# Sheet_3.net
KiCad netlist of a schematic drawn in Altium Designer
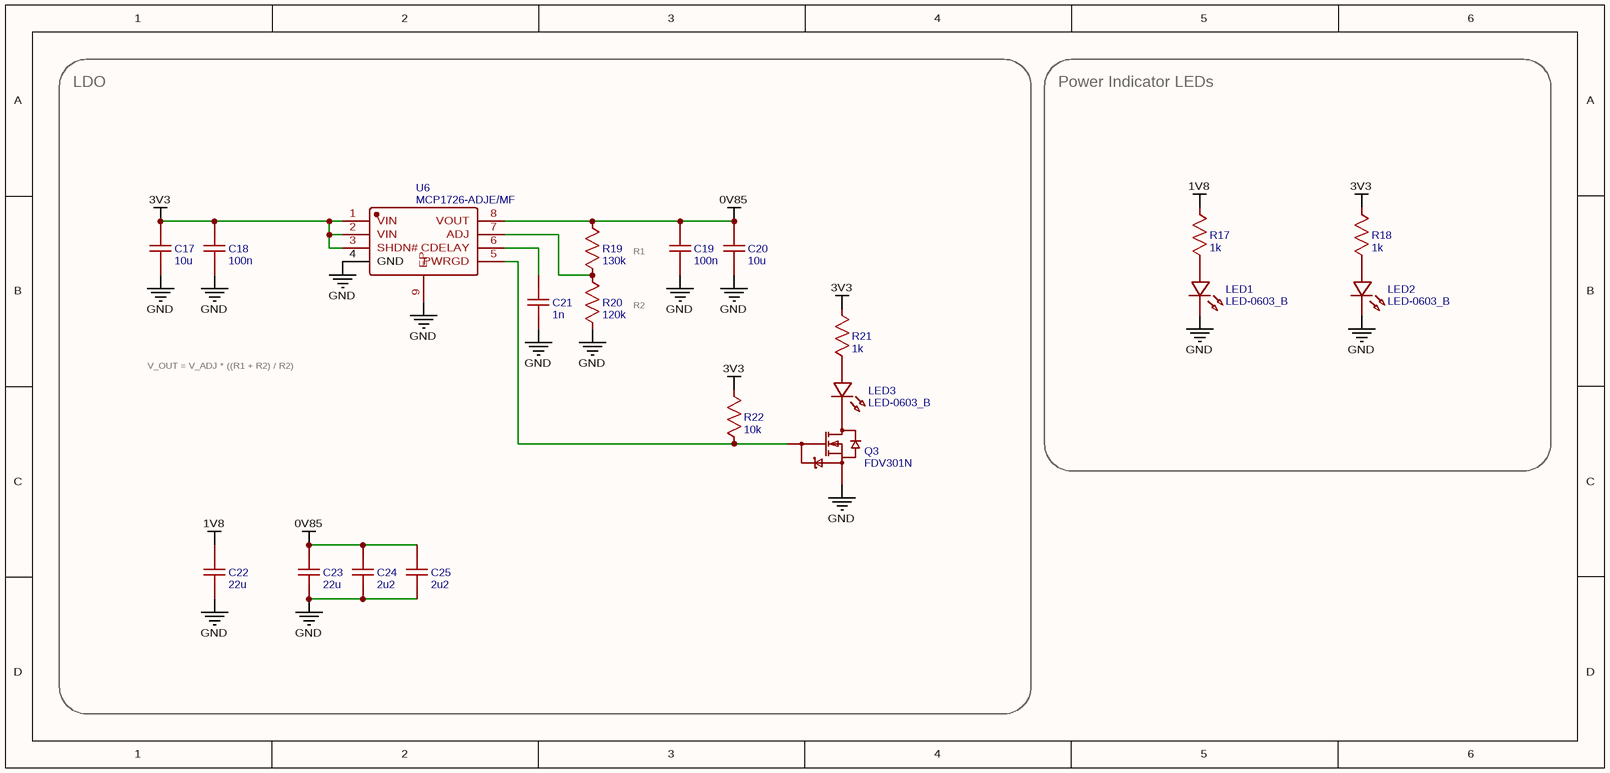
[diagram p0: Sheet_3.schdoc]

(export (version "E")
  (design (tool "Eeschema 10.0.6"))
  (components
    (comp (ref "C17")
      (value "10u")
      (footprint "CAPA-0402")
      (fields
        (field (name "BOM_SUPPLIER PART") "C87148")
        (field (name "BOM_MANUFACTURER PART") "JMK105CBJ106MV-F")
      )
      (libsource (lib "altium-import") (part "root_1_10u_"))
    )
    (comp (ref "C18")
      (value "100n")
      (footprint "CAPA-0402")
      (fields
        (field (name "BOM_SUPPLIER PART") "C307331")
        (field (name "BOM_MANUFACTURER PART") "CL05B104KB54PNC")
      )
      (libsource (lib "altium-import") (part "root_1_100n_"))
    )
    (comp (ref "C19")
      (value "100n")
      (footprint "CAPA-0402")
      (fields
        (field (name "BOM_SUPPLIER PART") "C307331")
        (field (name "BOM_MANUFACTURER PART") "CL05B104KB54PNC")
      )
      (libsource (lib "altium-import") (part "root_1_100n_"))
    )
    (comp (ref "C20")
      (value "10u")
      (footprint "CAPA-0402")
      (fields
        (field (name "BOM_SUPPLIER PART") "C87148")
        (field (name "BOM_MANUFACTURER PART") "JMK105CBJ106MV-F")
      )
      (libsource (lib "altium-import") (part "root_1_10u_"))
    )
    (comp (ref "C21")
      (value "1n")
      (footprint "CAPA-0402")
      (fields
        (field (name "BOM_SUPPLIER PART") "C113780")
        (field (name "BOM_MANUFACTURER PART") "CC0402JRNPO9BN102")
      )
      (libsource (lib "altium-import") (part "root_1_1n_"))
    )
    (comp (ref "C22")
      (value "22u")
      (footprint "CAPA-1206")
      (fields
        (field (name "BOM_SUPPLIER PART") "C12891")
        (field (name "BOM_MANUFACTURER PART") "CL31A226KAHNNNE")
      )
      (libsource (lib "altium-import") (part "root_1_22u_"))
    )
    (comp (ref "C23")
      (value "22u")
      (footprint "CAPA-1206")
      (fields
        (field (name "BOM_SUPPLIER PART") "C12891")
        (field (name "BOM_MANUFACTURER PART") "CL31A226KAHNNNE")
      )
      (libsource (lib "altium-import") (part "root_1_22u_"))
    )
    (comp (ref "C24")
      (value "2u2")
      (footprint "CAPA-1206")
      (fields
        (field (name "BOM_SUPPLIER PART") "C50254")
        (field (name "BOM_MANUFACTURER PART") "CL31B225KBHNNNE")
      )
      (libsource (lib "altium-import") (part "root_1_2u2_"))
    )
    (comp (ref "C25")
      (value "2u2")
      (footprint "CAPA-1206")
      (fields
        (field (name "BOM_SUPPLIER PART") "C50254")
        (field (name "BOM_MANUFACTURER PART") "CL31B225KBHNNNE")
      )
      (libsource (lib "altium-import") (part "root_1_2u2_"))
    )
    (comp (ref "LED1")
      (value "LED-0603_B")
      (footprint "LED-0603")
      (fields (field (name "BOM_MANUFACTURER PART") "XL-0603QBC") (field (name "BOM_SUPPLIER PART") "C2288"))
      (libsource (lib "altium-import") (part "root_3_LED-0603_B_"))
    )
    (comp (ref "LED2")
      (value "LED-0603_B")
      (footprint "LED-0603")
      (fields (field (name "BOM_MANUFACTURER PART") "XL-0603QBC") (field (name "BOM_SUPPLIER PART") "C2288"))
      (libsource (lib "altium-import") (part "root_3_LED-0603_B_"))
    )
    (comp (ref "LED3")
      (value "LED-0603_B")
      (footprint "LED-0603")
      (fields (field (name "BOM_MANUFACTURER PART") "XL-0603QBC") (field (name "BOM_SUPPLIER PART") "C2288"))
      (libsource (lib "altium-import") (part "root_3_LED-0603_B_"))
    )
    (comp (ref "Q3")
      (value "FDV301N")
      (footprint "SOT-23_L2.9-W1.3-P1.90-LS2.4-BR")
      (fields (field (name "BOM_SUPPLIER PART") "C15310"))
      (libsource (lib "altium-import") (part "root_0_FDV301N_"))
    )
    (comp (ref "R17")
      (value "1k")
      (footprint "RES-0402")
      (fields
        (field (name "BOM_SUPPLIER PART") "C11702")
        (field (name "BOM_MANUFACTURER PART") "0402WGF1001TCE")
      )
      (libsource (lib "altium-import") (part "root_1_1k_"))
    )
    (comp (ref "R18")
      (value "1k")
      (footprint "RES-0402")
      (fields
        (field (name "BOM_SUPPLIER PART") "C11702")
        (field (name "BOM_MANUFACTURER PART") "0402WGF1001TCE")
      )
      (libsource (lib "altium-import") (part "root_1_1k_"))
    )
    (comp (ref "R19")
      (value "130k")
      (footprint "RES-0402")
      (fields
        (field (name "BOM_SUPPLIER PART") "C52929")
        (field (name "BOM_MANUFACTURER PART") "0402WGF1303TCE")
      )
      (libsource (lib "altium-import") (part "root_1_130k_"))
    )
    (comp (ref "R20")
      (value "120k")
      (footprint "RES-0402")
      (fields
        (field (name "BOM_SUPPLIER PART") "C25750")
        (field (name "BOM_MANUFACTURER PART") "0402WGF1203TCE")
      )
      (libsource (lib "altium-import") (part "root_1_120k_"))
    )
    (comp (ref "R21")
      (value "1k")
      (footprint "RES-0402")
      (fields
        (field (name "BOM_SUPPLIER PART") "C11702")
        (field (name "BOM_MANUFACTURER PART") "0402WGF1001TCE")
      )
      (libsource (lib "altium-import") (part "root_1_1k_"))
    )
    (comp (ref "R22")
      (value "10k")
      (footprint "RES-0402")
      (fields
        (field (name "BOM_SUPPLIER PART") "C25744")
        (field (name "BOM_MANUFACTURER PART") "0402WGF1002TCE")
      )
      (libsource (lib "altium-import") (part "root_1_10k_"))
    )
    (comp (ref "U6")
      (value "MCP1726-ADJE/MF")
      (footprint "TDFN-8_L3.0-W3.0-P0.65-BL-EP")
      (fields (field (name "BOM_SUPPLIER PART") "C184287"))
      (libsource (lib "altium-import") (part "root_0_MCP1726-ADJE/MF_"))
    )
  )
  (nets
    (net (code "1") (name "0V85") (class "Default")
      (node (ref "C19") (pin "2") (pinfunction "2_2") (pintype "passive"))
      (node (ref "C20") (pin "2") (pinfunction "2_2") (pintype "passive"))
      (node (ref "C23") (pin "2") (pinfunction "2_2") (pintype "passive"))
      (node (ref "C24") (pin "2") (pinfunction "2_2") (pintype "passive"))
      (node (ref "C25") (pin "2") (pinfunction "2_2") (pintype "passive"))
      (node (ref "R19") (pin "2") (pinfunction "2_2") (pintype "passive"))
      (node (ref "U6") (pin "8") (pinfunction "VOUT_8") (pintype "passive"))
    )
    (net (code "2") (name "1V8") (class "Default")
      (node (ref "C22") (pin "2") (pinfunction "2_2") (pintype "passive"))
      (node (ref "R17") (pin "2") (pinfunction "2_2") (pintype "passive"))
    )
    (net (code "3") (name "3V3") (class "Default")
      (node (ref "C17") (pin "2") (pinfunction "2_2") (pintype "passive"))
      (node (ref "C18") (pin "2") (pinfunction "2_2") (pintype "passive"))
      (node (ref "R18") (pin "2") (pinfunction "2_2") (pintype "passive"))
      (node (ref "R21") (pin "2") (pinfunction "2_2") (pintype "passive"))
      (node (ref "R22") (pin "2") (pinfunction "2_2") (pintype "passive"))
      (node (ref "U6") (pin "1") (pinfunction "VIN_1") (pintype "passive"))
      (node (ref "U6") (pin "2") (pinfunction "VIN_2") (pintype "passive"))
      (node (ref "U6") (pin "3") (pinfunction "SHDN#_3") (pintype "passive"))
    )
    (net (code "4") (name "GND") (class "Default")
      (node (ref "C17") (pin "1") (pinfunction "1_1") (pintype "passive"))
      (node (ref "C18") (pin "1") (pinfunction "1_1") (pintype "passive"))
      (node (ref "C19") (pin "1") (pinfunction "1_1") (pintype "passive"))
      (node (ref "C20") (pin "1") (pinfunction "1_1") (pintype "passive"))
      (node (ref "C21") (pin "1") (pinfunction "1_1") (pintype "passive"))
      (node (ref "C22") (pin "1") (pinfunction "1_1") (pintype "passive"))
      (node (ref "C23") (pin "1") (pinfunction "1_1") (pintype "passive"))
      (node (ref "C24") (pin "1") (pinfunction "1_1") (pintype "passive"))
      (node (ref "C25") (pin "1") (pinfunction "1_1") (pintype "passive"))
      (node (ref "LED1") (pin "2") (pinfunction "2_2") (pintype "passive"))
      (node (ref "LED2") (pin "2") (pinfunction "2_2") (pintype "passive"))
      (node (ref "Q3") (pin "2") (pinfunction "S_2") (pintype "passive"))
      (node (ref "R20") (pin "1") (pinfunction "1_1") (pintype "passive"))
      (node (ref "U6") (pin "4") (pinfunction "GND_4") (pintype "passive"))
      (node (ref "U6") (pin "9") (pinfunction "EP_9") (pintype "passive"))
    )
    (net (code "5") (name "Net-(LED1-Pad1)") (class "Default")
      (node (ref "LED1") (pin "1") (pinfunction "1_1") (pintype "passive"))
      (node (ref "R17") (pin "1") (pinfunction "1_1") (pintype "passive"))
    )
    (net (code "6") (name "Net-(LED2-Pad1)") (class "Default")
      (node (ref "LED2") (pin "1") (pinfunction "1_1") (pintype "passive"))
      (node (ref "R18") (pin "1") (pinfunction "1_1") (pintype "passive"))
    )
    (net (code "7") (name "Net-(LED3-Pad1)") (class "Default")
      (node (ref "LED3") (pin "1") (pinfunction "1_1") (pintype "passive"))
      (node (ref "R21") (pin "1") (pinfunction "1_1") (pintype "passive"))
    )
    (net (code "8") (name "Net-(Q3-D)") (class "Default")
      (node (ref "LED3") (pin "2") (pinfunction "2_2") (pintype "passive"))
      (node (ref "Q3") (pin "3") (pinfunction "D_3") (pintype "passive"))
    )
    (net (code "9") (name "Net-(Q3-G)") (class "Default")
      (node (ref "Q3") (pin "1") (pinfunction "G_1") (pintype "passive"))
      (node (ref "R22") (pin "1") (pinfunction "1_1") (pintype "passive"))
      (node (ref "U6") (pin "5") (pinfunction "PWRGD_5") (pintype "passive"))
    )
    (net (code "10") (name "Net-(U6-ADJ)") (class "Default")
      (node (ref "R19") (pin "1") (pinfunction "1_1") (pintype "passive"))
      (node (ref "R20") (pin "2") (pinfunction "2_2") (pintype "passive"))
      (node (ref "U6") (pin "7") (pinfunction "ADJ_7") (pintype "passive"))
    )
    (net (code "11") (name "Net-(U6-CDELAY)") (class "Default")
      (node (ref "C21") (pin "2") (pinfunction "2_2") (pintype "passive"))
      (node (ref "U6") (pin "6") (pinfunction "CDELAY_6") (pintype "passive"))
    )
  )
)
